# Input_Sensor_E3J-DS30M2.net
KiCad netlist of a schematic drawn in Altium Designer
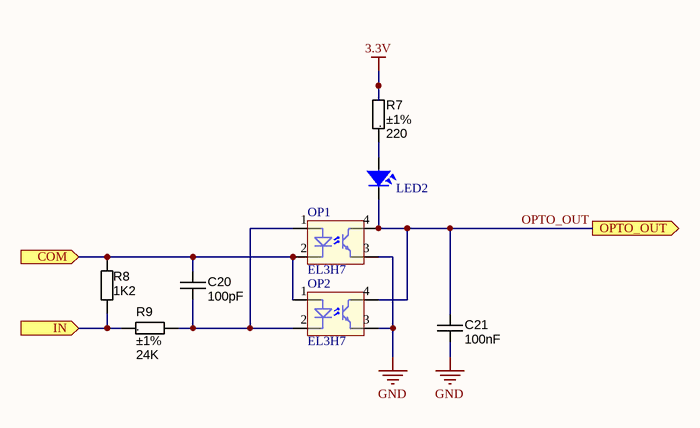
[diagram p0: Input_Sensor E3J-DS30M2.SchDoc]

(export (version "E")
  (design (tool "Eeschema 10.0.6"))
  (components
    (comp (ref "C20")
      (value "100pF")
      (footprint "CAPC1608X90N")
      (description "100pF ±5% 100V Ceramic Capacitor C0G, NP0 0603 (1608 Metric)")
      (fields (field (name "TOLERANCE") "±5%"))
      (libsource (lib "SangMV") (part "CAPC_100pF_0603_C0G_NP0_100V_5%"))
    )
    (comp (ref "C21")
      (value "100nF")
      (footprint "CAPC1608X90N")
      (description "0.1µF ±10% 50V Ceramic Capacitor X7R 0603 (1608 Metric)")
      (fields (field (name "TOLERANCE") "±10%"))
      (libsource (lib "All Library") (part "CAPC_100nF_0603_X7R_50V_10%"))
    )
    (comp (ref "LED2")
      (value "LED")
      (footprint "LED-0805-Green")
      (libsource (lib "thu vien 3d") (part "LED SMD"))
    )
    (comp (ref "OP1")
      (value "EL3H7")
      (footprint "IC_SMD_SSOP4_NEW")
      (description "Photo Transistor")
      (libsource (lib "All Library") (part "OPTO_EL3H7"))
    )
    (comp (ref "OP2")
      (value "EL3H7")
      (footprint "IC_SMD_SSOP4_NEW")
      (description "Photo Transistor")
      (libsource (lib "All Library") (part "OPTO_EL3H7"))
    )
    (comp (ref "R7")
      (value "220")
      (footprint "RESC1608X55N")
      (fields
        (field (name "MANUFACTURER") "Stackpole Electronics Inc")
        (field (name "MANUFACTURER PART NUMBER") "RMCF0603FT10K0")
        (field (name "TOLERANCE") "±1%")
        (field (name "Comment") "10K_0603_1%")
      )
      (libsource (lib "All Library") (part "RES_10K_0603_1%"))
    )
    (comp (ref "R8")
      (value "1K2")
      (footprint "RES_2W_AXIAL_11x4_STAND")
      (description "Resistor THD 390 Ohm 2W 5% Metal Film")
      (fields (field (name "TOLERANCE") "±5%") (field (name "Comment") "Metal Film"))
      (libsource (lib "All Library") (part "RES_390R_Axial_2W_5%"))
    )
    (comp (ref "R9")
      (value "24K")
      (footprint "RESC2012X70N")
      (description "24 kOhms ±1% 0.125W, 1/8W Chip Resistor 0805 (2012 Metric) Automotive AEC-Q200 Thick Film")
      (fields
        (field (name "MANUFACTURER") "Stackpole Electronics Inc")
        (field (name "MANUFACTURER PART NUMBER") "RMCF0805FT10K5")
        (field (name "TOLERANCE") "±1%")
      )
      (libsource (lib "All Library") (part "RES_24K_0805_1%"))
    )
  )
  (nets
    (net (code "1") (name "/COM") (class "Default")
      (node (ref "C20") (pin "1") (pintype "passive"))
      (node (ref "OP1") (pin "2") (pinfunction "K_2") (pintype "passive"))
      (node (ref "OP2") (pin "1") (pinfunction "A_1") (pintype "passive"))
      (node (ref "R8") (pin "1") (pinfunction "1_1") (pintype "passive"))
    )
    (net (code "2") (name "/IN") (class "Default")
      (node (ref "R8") (pin "2") (pinfunction "2_2") (pintype "passive"))
      (node (ref "R9") (pin "1") (pinfunction "1_1") (pintype "passive"))
    )
    (net (code "3") (name "/OPTO_OUT") (class "Default")
      (node (ref "C21") (pin "1") (pintype "passive"))
      (node (ref "LED2") (pin "2") (pinfunction "2_2") (pintype "passive"))
      (node (ref "OP1") (pin "4") (pinfunction "C_4") (pintype "passive"))
      (node (ref "OP2") (pin "4") (pinfunction "C_4") (pintype "passive"))
    )
    (net (code "4") (name "3.3V") (class "Default")
      (node (ref "R7") (pin "2") (pinfunction "2_2") (pintype "passive"))
    )
    (net (code "5") (name "GND") (class "Default")
      (node (ref "C21") (pin "2") (pintype "passive"))
      (node (ref "OP1") (pin "3") (pinfunction "E_3") (pintype "passive"))
      (node (ref "OP2") (pin "3") (pinfunction "E_3") (pintype "passive"))
    )
    (net (code "6") (name "Net-(LED2-Pad1)") (class "Default")
      (node (ref "LED2") (pin "1") (pinfunction "1_1") (pintype "passive"))
      (node (ref "R7") (pin "1") (pinfunction "1_1") (pintype "passive"))
    )
    (net (code "7") (name "Net-(OP1-A)") (class "Default")
      (node (ref "C20") (pin "2") (pintype "passive"))
      (node (ref "OP1") (pin "1") (pinfunction "A_1") (pintype "passive"))
      (node (ref "OP2") (pin "2") (pinfunction "K_2") (pintype "passive"))
      (node (ref "R9") (pin "2") (pinfunction "2_2") (pintype "passive"))
    )
  )
)
